# PCB_boost_converter.net
KiCad netlist of a schematic drawn in EAGLE
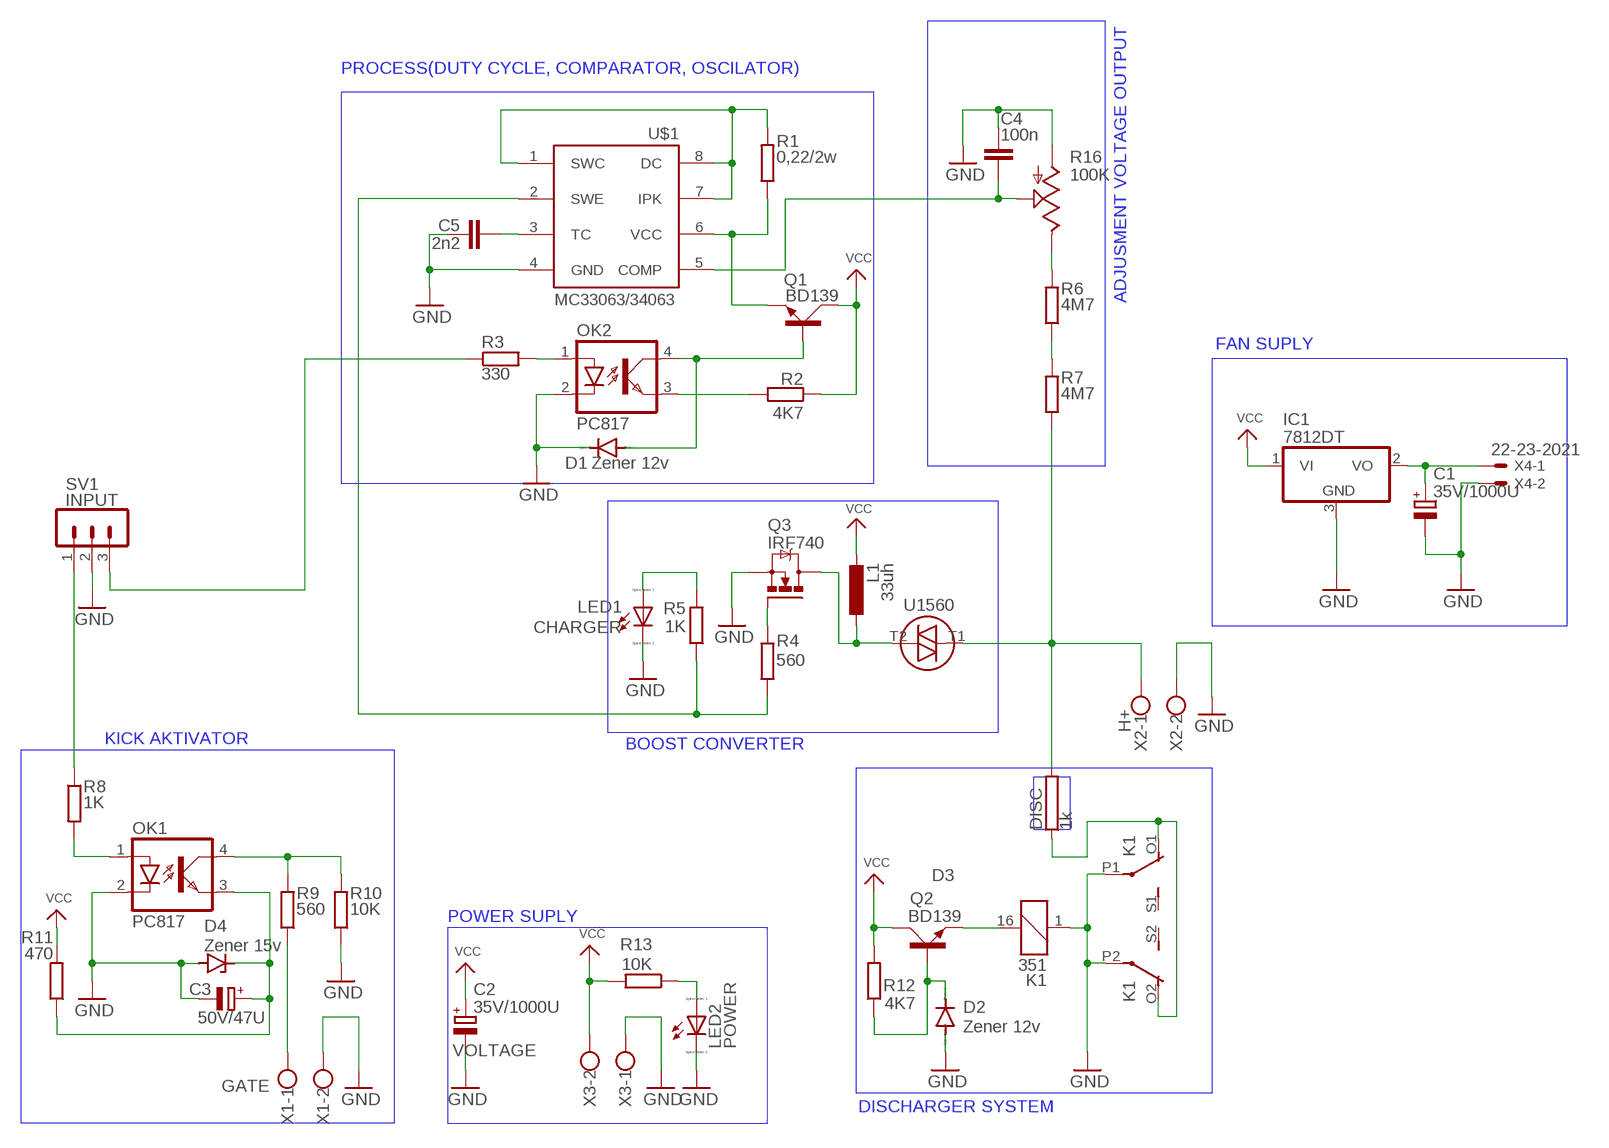
[diagram p0: schematic, sheet 1]

(export (version "E")
  (design (tool "Eeschema 10.0.6"))
  (components
    (comp (ref "C1")
      (value "35V/1000U")
      (footprint "eagle-import:E2,5-7")
      (libsource (lib "eagle-import") (part "CPOL-EUE2.5-7"))
    )
    (comp (ref "C2")
      (value "35V/1000U")
      (footprint "eagle-import:E2,5-7")
      (libsource (lib "eagle-import") (part "CPOL-EUE2.5-7"))
    )
    (comp (ref "C3")
      (value "50V/47U")
      (footprint "eagle-import:153CLV-0810")
      (libsource (lib "eagle-import") (part "CPOL-EU153CLV-0810"))
    )
    (comp (ref "C4")
      (value "100n")
      (footprint "eagle-import:C0805K")
      (libsource (lib "eagle-import") (part "C-EUC0805K"))
    )
    (comp (ref "C5")
      (value "2n2")
      (footprint "eagle-import:C0805K")
      (libsource (lib "eagle-import") (part "C-EUC0805K"))
    )
    (comp (ref "D1")
      (value "Zener 12v")
      (footprint "eagle-import:DO35-7")
      (libsource (lib "eagle-import") (part "1N4148DO35-7"))
    )
    (comp (ref "D2")
      (value "Zener 12v")
      (footprint "eagle-import:DO35-7")
      (libsource (lib "eagle-import") (part "1N4148DO35-7"))
    )
    (comp (ref "D3")
      (value "U1560")
      (footprint "eagle-import:BR210S")
      (libsource (lib "eagle-import") (part "BR210"))
    )
    (comp (ref "D4")
      (value "Zener 15v")
      (footprint "eagle-import:DO35Z10")
      (libsource (lib "eagle-import") (part "BZX55"))
    )
    (comp (ref "DISC")
      (value "1k")
      (footprint "eagle-import:RWM10X64")
      (libsource (lib "eagle-import") (part "RRWM10X64"))
    )
    (comp (ref "IC1")
      (value "7812DT")
      (footprint "eagle-import:TO252")
      (libsource (lib "eagle-import") (part "78DT12"))
    )
    (comp (ref "K1")
      (value "351")
      (footprint "eagle-import:351")
      (libsource (lib "eagle-import") (part "351"))
    )
    (comp (ref "L1")
      (value "33uh")
      (footprint "eagle-import:TJ3-U2")
      (libsource (lib "eagle-import") (part "L-EUTJ3-U2"))
    )
    (comp (ref "LED1")
      (value "CHARGER")
      (footprint "eagle-import:LED_1206")
      (libsource (lib "eagle-import") (part "LED_E"))
    )
    (comp (ref "LED2")
      (value "POWER")
      (footprint "eagle-import:LED_1206")
      (libsource (lib "eagle-import") (part "LED_E"))
    )
    (comp (ref "OK1")
      (value "PC817")
      (footprint "eagle-import:DIL04")
      (fields (field (name "MPN") "PC817X4J000F"))
      (libsource (lib "eagle-import") (part "PC817"))
    )
    (comp (ref "OK2")
      (value "PC817")
      (footprint "eagle-import:DIL04")
      (fields (field (name "MPN") "PC817X4J000F"))
      (libsource (lib "eagle-import") (part "PC817"))
    )
    (comp (ref "Q1")
      (value "BD139")
      (footprint "eagle-import:TO126AV")
      (libsource (lib "eagle-import") (part "BD139"))
    )
    (comp (ref "Q2")
      (value "BD139")
      (footprint "eagle-import:TO126AV")
      (libsource (lib "eagle-import") (part "BD139"))
    )
    (comp (ref "Q3")
      (value "IRF740")
      (footprint "eagle-import:TO220BV")
      (libsource (lib "eagle-import") (part "IRF740"))
    )
    (comp (ref "R1")
      (value "0,22/2w")
      (footprint "eagle-import:M1206")
      (libsource (lib "eagle-import") (part "R-EU_M1206"))
    )
    (comp (ref "R2")
      (value "4K7")
      (footprint "eagle-import:M1206")
      (libsource (lib "eagle-import") (part "R-EU_M1206"))
    )
    (comp (ref "R3")
      (value "330")
      (footprint "eagle-import:M1206")
      (libsource (lib "eagle-import") (part "R-EU_M1206"))
    )
    (comp (ref "R4")
      (value "560")
      (footprint "eagle-import:M1206")
      (libsource (lib "eagle-import") (part "R-EU_M1206"))
    )
    (comp (ref "R5")
      (value "1K")
      (footprint "eagle-import:M1206")
      (libsource (lib "eagle-import") (part "R-EU_M1206"))
    )
    (comp (ref "R6")
      (value "4M7")
      (footprint "eagle-import:0309_10")
      (libsource (lib "eagle-import") (part "R-EU_0309/10"))
    )
    (comp (ref "R7")
      (value "4M7")
      (footprint "eagle-import:0309_10")
      (libsource (lib "eagle-import") (part "R-EU_0309/10"))
    )
    (comp (ref "R8")
      (value "1K")
      (footprint "eagle-import:M1206")
      (libsource (lib "eagle-import") (part "R-EU_M1206"))
    )
    (comp (ref "R9")
      (value "560")
      (footprint "eagle-import:M1206")
      (libsource (lib "eagle-import") (part "R-EU_M1206"))
    )
    (comp (ref "R10")
      (value "10K")
      (footprint "eagle-import:M1206")
      (libsource (lib "eagle-import") (part "R-EU_M1206"))
    )
    (comp (ref "R11")
      (value "470")
      (footprint "eagle-import:M1206")
      (libsource (lib "eagle-import") (part "R-EU_M1206"))
    )
    (comp (ref "R12")
      (value "4K7")
      (footprint "eagle-import:M1206")
      (libsource (lib "eagle-import") (part "R-EU_M1206"))
    )
    (comp (ref "R13")
      (value "10K")
      (footprint "eagle-import:M1206")
      (libsource (lib "eagle-import") (part "R-EU_M1206"))
    )
    (comp (ref "R16")
      (value "100K")
      (footprint "eagle-import:CA6V")
      (libsource (lib "eagle-import") (part "TRIM_US-CA6V"))
    )
    (comp (ref "SV1")
      (value "INPUT")
      (footprint "eagle-import:MA03-1")
      (libsource (lib "eagle-import") (part "MA03-1"))
    )
    (comp (ref "U$1")
      (value "MC33063/MC34063D")
      (footprint "eagle-import:SO08")
      (libsource (lib "eagle-import") (part "MC33063/MC34063D"))
    )
    (comp (ref "X1")
      (value "GATE")
      (footprint "eagle-import:W237-102")
      (fields (field (name "MPN") "237-102"))
      (libsource (lib "eagle-import") (part "W237-102"))
    )
    (comp (ref "X2")
      (value "H+")
      (footprint "eagle-import:W237-102")
      (fields (field (name "MPN") "237-102"))
      (libsource (lib "eagle-import") (part "W237-102"))
    )
    (comp (ref "X3")
      (value "VOLTAGE")
      (footprint "eagle-import:W237-102")
      (fields (field (name "MPN") "237-102"))
      (libsource (lib "eagle-import") (part "W237-102"))
    )
    (comp (ref "X4")
      (value "22-23-2021")
      (footprint "eagle-import:22-23-2021")
      (fields (field (name "MF") "MOLEX"))
      (libsource (lib "eagle-import") (part "22-23-2021"))
    )
  )
  (nets
    (net (code "1") (name "GND") (class "Default")
      (node (ref "C1") (pin "-") (pinfunction "-_-") (pintype "passive"))
      (node (ref "C2") (pin "-") (pinfunction "-_-") (pintype "passive"))
      (node (ref "C3") (pin "-") (pinfunction "-_-") (pintype "passive"))
      (node (ref "C4") (pin "1") (pinfunction "1_1") (pintype "passive"))
      (node (ref "C5") (pin "1") (pinfunction "1_1") (pintype "passive"))
      (node (ref "D1") (pin "C") (pinfunction "C_C") (pintype "passive"))
      (node (ref "D2") (pin "A") (pinfunction "A_A") (pintype "passive"))
      (node (ref "D4") (pin "A") (pinfunction "A_A") (pintype "passive"))
      (node (ref "IC1") (pin "3") (pinfunction "GND_3") (pintype "passive"))
      (node (ref "K1") (pin "1") (pinfunction "1_1") (pintype "passive"))
      (node (ref "K1") (pin "P1") (pinfunction "P_P1") (pintype "passive"))
      (node (ref "K1") (pin "P2") (pinfunction "P_P2") (pintype "passive"))
      (node (ref "LED1") (pin "C") (pinfunction "C_C") (pintype "passive"))
      (node (ref "LED2") (pin "C") (pinfunction "C_C") (pintype "passive"))
      (node (ref "OK1") (pin "2") (pinfunction "C_2") (pintype "passive"))
      (node (ref "OK2") (pin "2") (pinfunction "C_2") (pintype "passive"))
      (node (ref "Q3") (pin "S") (pinfunction "S_S") (pintype "passive"))
      (node (ref "R10") (pin "1") (pinfunction "1_1") (pintype "passive"))
      (node (ref "R16") (pin "A") (pinfunction "A_A") (pintype "passive"))
      (node (ref "SV1") (pin "2") (pinfunction "2_2") (pintype "passive"))
      (node (ref "U$1") (pin "4") (pinfunction "GND_4") (pintype "power_in"))
      (node (ref "X1") (pin "2") (pinfunction "KL_2") (pintype "passive"))
      (node (ref "X2") (pin "2") (pinfunction "KL_2") (pintype "passive"))
      (node (ref "X3") (pin "1") (pinfunction "KL_1") (pintype "passive"))
      (node (ref "X4") (pin "2") (pinfunction "S_2") (pintype "passive"))
    )
    (net (code "2") (name "Net-(D2-PadC)") (class "Default")
      (node (ref "D2") (pin "C") (pinfunction "C_C") (pintype "passive"))
      (node (ref "Q2") (pin "B") (pinfunction "B_B") (pintype "passive"))
      (node (ref "R12") (pin "1") (pinfunction "1_1") (pintype "passive"))
    )
    (net (code "3") (name "Net-(D3-PadT2)") (class "Default")
      (node (ref "D3") (pin "T2") (pinfunction "T2_T2") (pintype "passive"))
      (node (ref "L1") (pin "1") (pinfunction "1_1") (pintype "passive"))
      (node (ref "Q3") (pin "D") (pinfunction "D_D") (pintype "passive"))
    )
    (net (code "4") (name "Net-(IC1-VO)") (class "Default")
      (node (ref "C1") (pin "+") (pinfunction "+_+") (pintype "passive"))
      (node (ref "IC1") (pin "2") (pinfunction "VO_2") (pintype "passive"))
      (node (ref "X4") (pin "1") (pinfunction "S_1") (pintype "passive"))
    )
    (net (code "5") (name "Net-(K1A-2)") (class "Default")
      (node (ref "K1") (pin "16") (pinfunction "2_16") (pintype "passive"))
      (node (ref "Q2") (pin "E") (pinfunction "E_E") (pintype "passive"))
    )
    (net (code "6") (name "Net-(K1B-O)") (class "Default")
      (node (ref "DISC") (pin "1") (pinfunction "1_1") (pintype "passive"))
      (node (ref "K1") (pin "O1") (pinfunction "O_O1") (pintype "passive"))
      (node (ref "K1") (pin "O2") (pinfunction "O_O2") (pintype "passive"))
    )
    (net (code "7") (name "Net-(LED1-PadA)") (class "Default")
      (node (ref "LED1") (pin "A") (pinfunction "A_A") (pintype "passive"))
      (node (ref "R5") (pin "2") (pinfunction "2_2") (pintype "passive"))
    )
    (net (code "8") (name "Net-(LED2-PadA)") (class "Default")
      (node (ref "LED2") (pin "A") (pinfunction "A_A") (pintype "passive"))
      (node (ref "R13") (pin "1") (pinfunction "1_1") (pintype "passive"))
    )
    (net (code "9") (name "Net-(OK1-A)") (class "Default")
      (node (ref "OK1") (pin "1") (pinfunction "A_1") (pintype "passive"))
      (node (ref "R8") (pin "2") (pinfunction "2_2") (pintype "passive"))
    )
    (net (code "10") (name "Net-(OK1-COL)") (class "Default")
      (node (ref "OK1") (pin "4") (pinfunction "COL_4") (pintype "passive"))
      (node (ref "R10") (pin "2") (pinfunction "2_2") (pintype "passive"))
      (node (ref "R9") (pin "2") (pinfunction "2_2") (pintype "passive"))
    )
    (net (code "11") (name "Net-(OK1-EMIT)") (class "Default")
      (node (ref "C3") (pin "+") (pinfunction "+_+") (pintype "passive"))
      (node (ref "D4") (pin "C") (pinfunction "C_C") (pintype "passive"))
      (node (ref "OK1") (pin "3") (pinfunction "EMIT_3") (pintype "passive"))
      (node (ref "R11") (pin "1") (pinfunction "1_1") (pintype "passive"))
    )
    (net (code "12") (name "Net-(OK2-A)") (class "Default")
      (node (ref "OK2") (pin "1") (pinfunction "A_1") (pintype "passive"))
      (node (ref "R3") (pin "2") (pinfunction "2_2") (pintype "passive"))
    )
    (net (code "13") (name "Net-(OK2-COL)") (class "Default")
      (node (ref "D1") (pin "A") (pinfunction "A_A") (pintype "passive"))
      (node (ref "OK2") (pin "4") (pinfunction "COL_4") (pintype "passive"))
      (node (ref "Q1") (pin "B") (pinfunction "B_B") (pintype "passive"))
    )
    (net (code "14") (name "Net-(OK2-EMIT)") (class "Default")
      (node (ref "OK2") (pin "3") (pinfunction "EMIT_3") (pintype "passive"))
      (node (ref "R2") (pin "2") (pinfunction "2_2") (pintype "passive"))
    )
    (net (code "15") (name "Net-(Q3-PadG)") (class "Default")
      (node (ref "Q3") (pin "G") (pinfunction "G_G") (pintype "passive"))
      (node (ref "R4") (pin "1") (pinfunction "1_1") (pintype "passive"))
    )
    (net (code "16") (name "Net-(R3-Pad1)") (class "Default")
      (node (ref "R3") (pin "1") (pinfunction "1_1") (pintype "passive"))
      (node (ref "SV1") (pin "3") (pinfunction "3_3") (pintype "passive"))
    )
    (net (code "17") (name "Net-(R6-Pad1)") (class "Default")
      (node (ref "R6") (pin "1") (pinfunction "1_1") (pintype "passive"))
      (node (ref "R7") (pin "2") (pinfunction "2_2") (pintype "passive"))
    )
    (net (code "18") (name "Net-(R8-Pad1)") (class "Default")
      (node (ref "R8") (pin "1") (pinfunction "1_1") (pintype "passive"))
      (node (ref "SV1") (pin "1") (pinfunction "1_1") (pintype "passive"))
    )
    (net (code "19") (name "Net-(R16-PadE)") (class "Default")
      (node (ref "R16") (pin "E") (pinfunction "E_E") (pintype "passive"))
      (node (ref "R6") (pin "2") (pinfunction "2_2") (pintype "passive"))
    )
    (net (code "20") (name "Net-(U$1-COMP)") (class "Default")
      (node (ref "C4") (pin "2") (pinfunction "2_2") (pintype "passive"))
      (node (ref "R16") (pin "S") (pinfunction "S_S") (pintype "passive"))
      (node (ref "U$1") (pin "5") (pinfunction "COMP_5") (pintype "input"))
    )
    (net (code "21") (name "Net-(U$1-DC)") (class "Default")
      (node (ref "R1") (pin "2") (pinfunction "2_2") (pintype "passive"))
      (node (ref "U$1") (pin "1") (pinfunction "SWC_1") (pintype "input"))
      (node (ref "U$1") (pin "7") (pinfunction "IPK_7") (pintype "bidirectional"))
      (node (ref "U$1") (pin "8") (pinfunction "DC_8") (pintype "input"))
    )
    (net (code "22") (name "Net-(U$1-SWE)") (class "Default")
      (node (ref "R4") (pin "2") (pinfunction "2_2") (pintype "passive"))
      (node (ref "R5") (pin "1") (pinfunction "1_1") (pintype "passive"))
      (node (ref "U$1") (pin "2") (pinfunction "SWE_2") (pintype "input"))
    )
    (net (code "23") (name "Net-(U$1-TC)") (class "Default")
      (node (ref "C5") (pin "2") (pinfunction "2_2") (pintype "passive"))
      (node (ref "U$1") (pin "3") (pinfunction "TC_3") (pintype "input"))
    )
    (net (code "24") (name "Net-(U$1-VCC)") (class "Default")
      (node (ref "Q1") (pin "E") (pinfunction "E_E") (pintype "passive"))
      (node (ref "R1") (pin "1") (pinfunction "1_1") (pintype "passive"))
      (node (ref "U$1") (pin "6") (pinfunction "VCC_6") (pintype "power_in"))
    )
    (net (code "25") (name "Net-(X1A-KL)") (class "Default")
      (node (ref "R9") (pin "1") (pinfunction "1_1") (pintype "passive"))
      (node (ref "X1") (pin "1") (pinfunction "KL_1") (pintype "passive"))
    )
    (net (code "26") (name "Net-(X2A-KL)") (class "Default")
      (node (ref "D3") (pin "T1") (pinfunction "T1_T1") (pintype "passive"))
      (node (ref "DISC") (pin "2") (pinfunction "2_2") (pintype "passive"))
      (node (ref "R7") (pin "1") (pinfunction "1_1") (pintype "passive"))
      (node (ref "X2") (pin "1") (pinfunction "KL_1") (pintype "passive"))
    )
    (net (code "27") (name "VCC") (class "Default")
      (node (ref "C2") (pin "+") (pinfunction "+_+") (pintype "passive"))
      (node (ref "IC1") (pin "1") (pinfunction "VI_1") (pintype "input"))
      (node (ref "L1") (pin "2") (pinfunction "2_2") (pintype "passive"))
      (node (ref "Q1") (pin "C") (pinfunction "C_C") (pintype "passive"))
      (node (ref "Q2") (pin "C") (pinfunction "C_C") (pintype "passive"))
      (node (ref "R11") (pin "2") (pinfunction "2_2") (pintype "passive"))
      (node (ref "R12") (pin "2") (pinfunction "2_2") (pintype "passive"))
      (node (ref "R13") (pin "2") (pinfunction "2_2") (pintype "passive"))
      (node (ref "R2") (pin "1") (pinfunction "1_1") (pintype "passive"))
      (node (ref "X3") (pin "2") (pinfunction "KL_2") (pintype "passive"))
    )
    (net (code "28") (name "unconnected-(K1B-S-PadS1)") (class "Default")
      (node (ref "K1") (pin "S1") (pinfunction "S_S1") (pintype "passive"))
    )
    (net (code "29") (name "unconnected-(K1C-S-PadS2)") (class "Default")
      (node (ref "K1") (pin "S2") (pinfunction "S_S2") (pintype "passive"))
    )
  )
)
